# Power_and_Connectors.net
KiCad netlist of a schematic drawn in Altium Designer
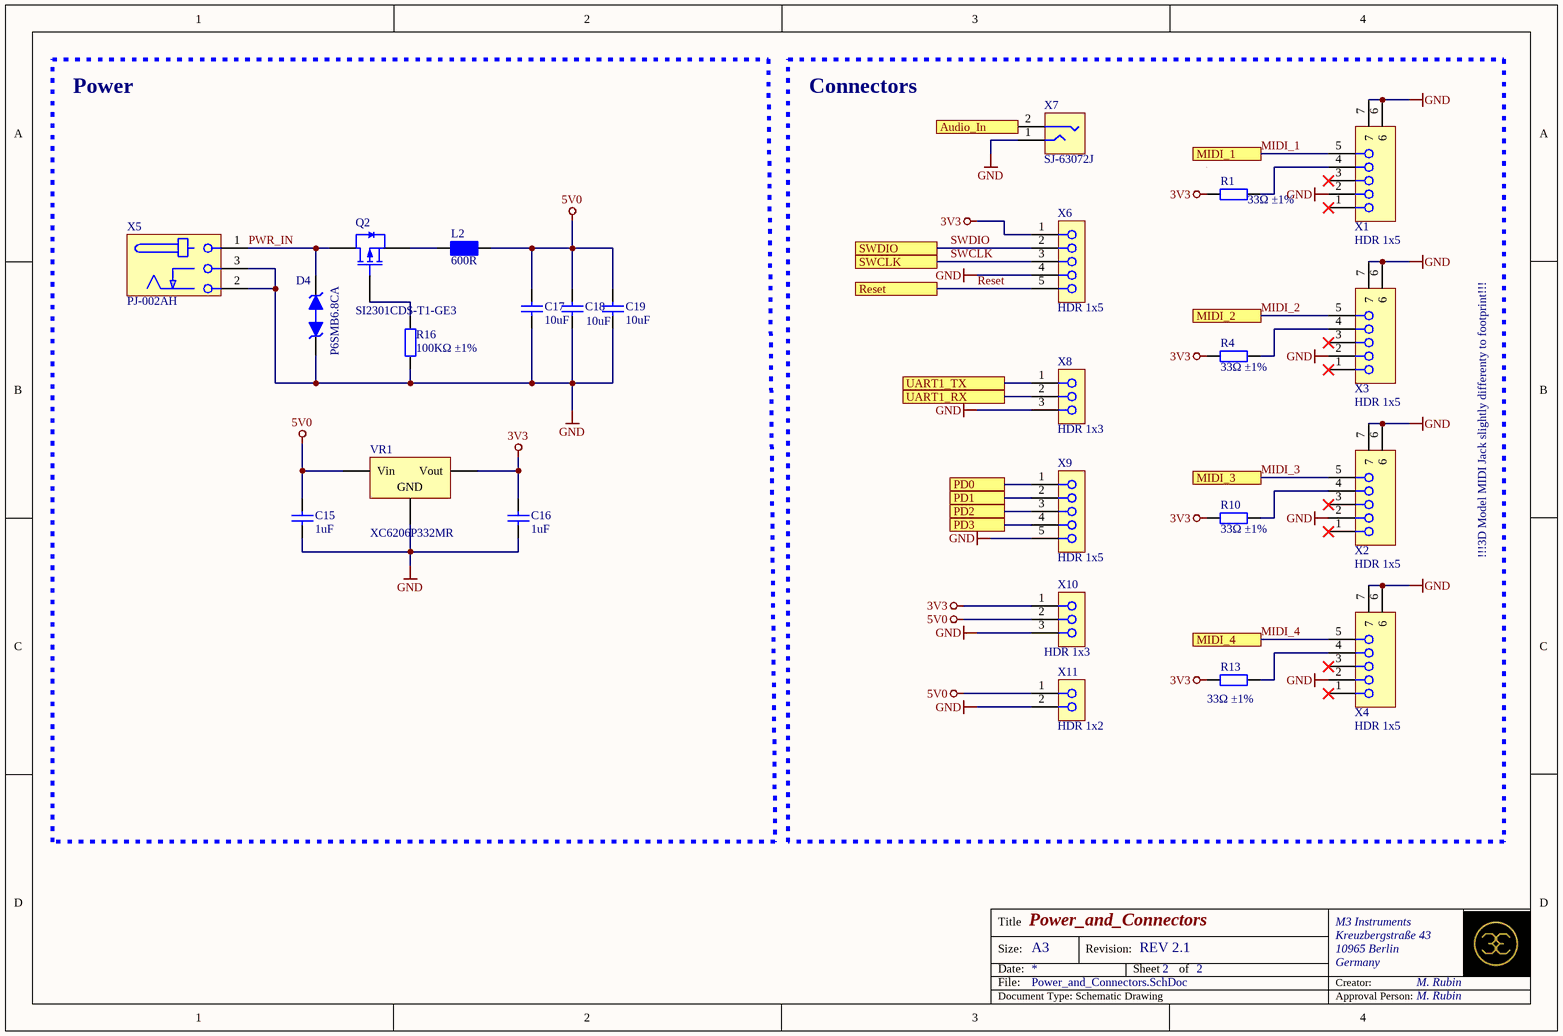
[diagram p0: Power_and_Connectors.SchDoc]

(export (version "E")
  (design (tool "Eeschema 10.0.6"))
  (components
    (comp (ref "C15")
      (value "1uF")
      (footprint "0603_C")
      (description "Chip capacitors")
      (fields
        (field (name "MANUFACTURER") "Samsung Electro-Mechanics")
        (field (name "PARTNUMBER") "CL10A105KB8NNNC")
      )
      (libsource (lib "Cap") (part "0603 1uF (105) 10% 50V"))
    )
    (comp (ref "C16")
      (value "1uF")
      (footprint "0603_C")
      (description "Chip capacitors")
      (fields
        (field (name "MANUFACTURER") "Samsung Electro-Mechanics")
        (field (name "PARTNUMBER") "CL10A105KB8NNNC")
      )
      (libsource (lib "Cap") (part "0603 1uF (105) 10% 50V"))
    )
    (comp (ref "C17")
      (value "10uF")
      (footprint "0805_C")
      (description "Chip capacitors")
      (fields
        (field (name "MANUFACTURER") "Samsung Electro-Mechanics")
        (field (name "PARTNUMBER") "CL21A106KAYNNNE")
      )
      (libsource (lib "Cap") (part "0805 10uF (106) 10% 25V"))
    )
    (comp (ref "C18")
      (value "10uF")
      (footprint "0805_C")
      (description "Chip capacitors")
      (fields
        (field (name "MANUFACTURER") "Samsung Electro-Mechanics")
        (field (name "PARTNUMBER") "CL21A106KAYNNNE")
      )
      (libsource (lib "Cap") (part "0805 10uF (106) 10% 25V"))
    )
    (comp (ref "C19")
      (value "10uF")
      (footprint "0805_C")
      (description "Chip capacitors")
      (fields
        (field (name "MANUFACTURER") "Samsung Electro-Mechanics")
        (field (name "PARTNUMBER") "CL21A106KAYNNNE")
      )
      (libsource (lib "Cap") (part "0805 10uF (106) 10% 25V"))
    )
    (comp (ref "D4")
      (value "P6SMB6.8CA")
      (footprint "SMB(DO-214AA)_S1")
      (description "TVS 6.8V")
      (fields (field (name "MANUFACTURER") "Brightking Elec"))
      (libsource (lib "Diodes") (part "DIO_P6SMB6.8CA"))
    )
    (comp (ref "L2")
      (value "600R")
      (footprint "INDC2012X85N")
      (description "Ferrite Beads 0805 600 OHM")
      (fields
        (field (name "MANUFACTURER") "Murata Electronics")
        (field (name "MANUFACTURER PART NUMBER") "BLM21AG601SN1D")
      )
      (libsource (lib "Inductors") (part "FB_600R_600mA_0805"))
    )
    (comp (ref "Q2")
      (value "SI2301CDS-T1-GE3")
      (footprint "SOT-23(SOT-23-3)")
      (description "MOS(场效应管)")
      (libsource (lib "MOS") (part "SI2301CDS-T1-GE3"))
    )
    (comp (ref "R1")
      (value "33Ω ±1%")
      (footprint "0603_R")
      (description "Chip resistor")
      (fields (field (name "MANUFACTURER") "Uniroyal Elec") (field (name "PARTNUMBER") "0603WAF330JT5E"))
      (libsource (lib "RES") (part "0603 33R (33R0) 1%"))
    )
    (comp (ref "R4")
      (value "33Ω ±1%")
      (footprint "0603_R")
      (description "Chip resistor")
      (fields (field (name "MANUFACTURER") "Uniroyal Elec") (field (name "PARTNUMBER") "0603WAF330JT5E"))
      (libsource (lib "RES") (part "0603 33R (33R0) 1%"))
    )
    (comp (ref "R10")
      (value "33Ω ±1%")
      (footprint "0603_R")
      (description "Chip resistor")
      (fields (field (name "MANUFACTURER") "Uniroyal Elec") (field (name "PARTNUMBER") "0603WAF330JT5E"))
      (libsource (lib "RES") (part "0603 33R (33R0) 1%"))
    )
    (comp (ref "R13")
      (value "33Ω ±1%")
      (footprint "0603_R")
      (description "Chip resistor")
      (fields (field (name "MANUFACTURER") "Uniroyal Elec") (field (name "PARTNUMBER") "0603WAF330JT5E"))
      (libsource (lib "RES") (part "0603 33R (33R0) 1%"))
    )
    (comp (ref "R16")
      (value "100KΩ ±1%")
      (footprint "0603_R")
      (description "Chip resistor")
      (fields (field (name "MANUFACTURER") "Uniroyal Elec") (field (name "PARTNUMBER") "0603WAF1003T5E"))
      (libsource (lib "RES") (part "0603 100K (1003) 1%"))
    )
    (comp (ref "VR1")
      (value "XC6206P332MR")
      (footprint "SOT-23-3L")
      (description "低压差线性稳压(LDO)")
      (libsource (lib "LDO") (part "SOT-23 XC6206P332MR"))
    )
    (comp (ref "X1")
      (value "HDR 1x5")
      (footprint "MABP 5S")
      (description "Board-to-Board-Steckverbinder, 2.54 mm, 5 Kontakt(e), Stiftleiste 1-Reihig")
      (fields (field (name "MANUFACTURER") "BKL") (field (name "MANUFACTURER PART NUMBER") "MABP 5S"))
      (libsource (lib "Connectors") (part "CON_HEADER_1X5"))
    )
    (comp (ref "X2")
      (value "HDR 1x5")
      (footprint "MABP 5S")
      (description "Board-to-Board-Steckverbinder, 2.54 mm, 5 Kontakt(e), Stiftleiste 1-Reihig")
      (fields (field (name "MANUFACTURER") "BKL") (field (name "MANUFACTURER PART NUMBER") "MABP 5S"))
      (libsource (lib "Connectors") (part "CON_HEADER_1X5"))
    )
    (comp (ref "X3")
      (value "HDR 1x5")
      (footprint "MABP 5S")
      (description "Board-to-Board-Steckverbinder, 2.54 mm, 5 Kontakt(e), Stiftleiste 1-Reihig")
      (fields (field (name "MANUFACTURER") "BKL") (field (name "MANUFACTURER PART NUMBER") "MABP 5S"))
      (libsource (lib "Connectors") (part "CON_HEADER_1X5"))
    )
    (comp (ref "X4")
      (value "HDR 1x5")
      (footprint "MABP 5S")
      (description "Board-to-Board-Steckverbinder, 2.54 mm, 5 Kontakt(e), Stiftleiste 1-Reihig")
      (fields (field (name "MANUFACTURER") "BKL") (field (name "MANUFACTURER PART NUMBER") "MABP 5S"))
      (libsource (lib "Connectors") (part "CON_HEADER_1X5"))
    )
    (comp (ref "X5")
      (value "PJ-002AH")
      (footprint "PJ3L1400H110")
      (description "DC Power Connectors Power Jacks, Inside Contact Diameter 2mm, Outside Contact Diameter 6,5mm")
      (fields
        (field (name "MANUFACTURER") "CUI Devices")
        (field (name "LUMIRA PART NUMBER") "S-QMS-SPEC-32532")
      )
      (libsource (lib "_CONNECTORS") (part "PJ-002AH"))
    )
    (comp (ref "X6")
      (value "HDR 1x5")
      (footprint "CON_HEADER2.54_1x5W")
      (description "Board-to-Board-Steckverbinder, 2.54 mm, 5 Kontakt(e), Stiftleiste 1-Reihig")
      (fields
        (field (name "MANUFACTURER") "Samtec")
        (field (name "MANUFACTURER PART NUMBER") "TSW-105-07-T-S")
      )
      (libsource (lib "_CONNECTORS") (part "CON_HEADER_1X5"))
    )
    (comp (ref "X7")
      (value "SJ-63072J")
      (footprint "CUI_SJ-63072J")
      (description "Telefon-Steckverbinder 1/4\"JACK HOR CHASIS CON PLSTC MNT")
      (fields (field (name "MANUFACTURER") "CUI Devices"))
      (libsource (lib "Connectors") (part "Phone_Jack_1/4"))
    )
    (comp (ref "X8")
      (value "HDR 1x3")
      (footprint "CON_HEADER2.54_1x3W")
      (description "Board-to-Board-Steckverbinder, 2.54 mm, 3 Kontakt(e), Stiftleiste 1-Reihig")
      (fields
        (field (name "MANUFACTURER") "Samtec")
        (field (name "MANUFACTURER PART NUMBER") "TSW-103-07-T-S")
      )
      (libsource (lib "_CONNECTORS") (part "CON_HEADER_1X3"))
    )
    (comp (ref "X9")
      (value "HDR 1x5")
      (footprint "CON_HEADER2.54_1x5W")
      (description "Board-to-Board-Steckverbinder, 2.54 mm, 5 Kontakt(e), Stiftleiste 1-Reihig")
      (fields
        (field (name "MANUFACTURER") "Samtec")
        (field (name "MANUFACTURER PART NUMBER") "TSW-105-07-T-S")
      )
      (libsource (lib "_CONNECTORS") (part "CON_HEADER_1X5"))
    )
    (comp (ref "X10")
      (value "HDR 1x3")
      (footprint "CON_HEADER2.54_1x3W")
      (description "Board-to-Board-Steckverbinder, 2.54 mm, 3 Kontakt(e), Stiftleiste 1-Reihig")
      (fields
        (field (name "MANUFACTURER") "Samtec")
        (field (name "MANUFACTURER PART NUMBER") "TSW-103-07-T-S")
      )
      (libsource (lib "_CONNECTORS") (part "CON_HEADER_1X3"))
    )
    (comp (ref "X11")
      (value "HDR 1x2")
      (footprint "CON_HEADER2.54_1x2W")
      (description "Board-to-Board-Steckverbinder, 2.54 mm, 2 Kontakt(e), Stiftleiste 1-Reihig")
      (fields
        (field (name "MANUFACTURER") "Samtec")
        (field (name "MANUFACTURER PART NUMBER") "TSW-102-07-T-S")
      )
      (libsource (lib "Connectors") (part "CON_HEADER_1X2"))
    )
  )
  (nets
    (net (code "1") (name "/Audio_In") (class "Default")
      (node (ref "X7") (pin "2") (pinfunction "2_2") (pintype "passive"))
    )
    (net (code "2") (name "/MIDI_1") (class "Default")
      (node (ref "X1") (pin "5") (pinfunction "5_5") (pintype "passive"))
    )
    (net (code "3") (name "/MIDI_2") (class "Default")
      (node (ref "X3") (pin "5") (pinfunction "5_5") (pintype "passive"))
    )
    (net (code "4") (name "/MIDI_3") (class "Default")
      (node (ref "X2") (pin "5") (pinfunction "5_5") (pintype "passive"))
    )
    (net (code "5") (name "/MIDI_4") (class "Default")
      (node (ref "X4") (pin "5") (pinfunction "5_5") (pintype "passive"))
    )
    (net (code "6") (name "/PD0") (class "Default")
      (node (ref "X9") (pin "1") (pinfunction "1_1") (pintype "passive"))
    )
    (net (code "7") (name "/PD1") (class "Default")
      (node (ref "X9") (pin "2") (pinfunction "2_2") (pintype "passive"))
    )
    (net (code "8") (name "/PD2") (class "Default")
      (node (ref "X9") (pin "3") (pinfunction "3_3") (pintype "passive"))
    )
    (net (code "9") (name "/PD3") (class "Default")
      (node (ref "X9") (pin "4") (pinfunction "4_4") (pintype "passive"))
    )
    (net (code "10") (name "/PWR_IN") (class "Default")
      (node (ref "D4") (pin "A2") (pinfunction "A2_A2") (pintype "passive"))
      (node (ref "Q2") (pin "3") (pinfunction "D_3") (pintype "passive"))
      (node (ref "X5") (pin "1") (pinfunction "1_1") (pintype "passive"))
    )
    (net (code "11") (name "/Reset") (class "Default")
      (node (ref "X6") (pin "5") (pinfunction "5_5") (pintype "passive"))
    )
    (net (code "12") (name "/SWCLK") (class "Default")
      (node (ref "X6") (pin "3") (pinfunction "3_3") (pintype "passive"))
    )
    (net (code "13") (name "/SWDIO") (class "Default")
      (node (ref "X6") (pin "2") (pinfunction "2_2") (pintype "passive"))
    )
    (net (code "14") (name "/UART1_RX") (class "Default")
      (node (ref "X8") (pin "2") (pinfunction "2_2") (pintype "passive"))
    )
    (net (code "15") (name "/UART1_TX") (class "Default")
      (node (ref "X8") (pin "1") (pinfunction "1_1") (pintype "passive"))
    )
    (net (code "16") (name "3V3") (class "Default")
      (node (ref "C16") (pin "2") (pinfunction "2_2") (pintype "passive"))
      (node (ref "R1") (pin "1") (pinfunction "1_1") (pintype "passive"))
      (node (ref "R10") (pin "1") (pinfunction "1_1") (pintype "passive"))
      (node (ref "R13") (pin "1") (pinfunction "1_1") (pintype "passive"))
      (node (ref "R4") (pin "1") (pinfunction "1_1") (pintype "passive"))
      (node (ref "VR1") (pin "2") (pinfunction "Vout_2") (pintype "passive"))
      (node (ref "X10") (pin "1") (pinfunction "1_1") (pintype "passive"))
      (node (ref "X6") (pin "1") (pinfunction "1_1") (pintype "passive"))
    )
    (net (code "17") (name "5V0") (class "Default")
      (node (ref "C15") (pin "2") (pinfunction "2_2") (pintype "passive"))
      (node (ref "C17") (pin "2") (pinfunction "2_2") (pintype "passive"))
      (node (ref "C18") (pin "2") (pinfunction "2_2") (pintype "passive"))
      (node (ref "C19") (pin "2") (pinfunction "2_2") (pintype "passive"))
      (node (ref "L2") (pin "2") (pinfunction "2_2") (pintype "passive"))
      (node (ref "VR1") (pin "3") (pinfunction "Vin_3") (pintype "passive"))
      (node (ref "X10") (pin "2") (pinfunction "2_2") (pintype "passive"))
      (node (ref "X11") (pin "1") (pinfunction "1_1") (pintype "passive"))
    )
    (net (code "18") (name "GND") (class "Default")
      (node (ref "C15") (pin "1") (pinfunction "1_1") (pintype "passive"))
      (node (ref "C16") (pin "1") (pinfunction "1_1") (pintype "passive"))
      (node (ref "C17") (pin "1") (pinfunction "1_1") (pintype "passive"))
      (node (ref "C18") (pin "1") (pinfunction "1_1") (pintype "passive"))
      (node (ref "C19") (pin "1") (pinfunction "1_1") (pintype "passive"))
      (node (ref "D4") (pin "A1") (pinfunction "A1_A1") (pintype "passive"))
      (node (ref "R16") (pin "1") (pinfunction "1_1") (pintype "passive"))
      (node (ref "VR1") (pin "1") (pinfunction "GND_1") (pintype "passive"))
      (node (ref "X1") (pin "2") (pinfunction "2_2") (pintype "passive"))
      (node (ref "X1") (pin "6") (pinfunction "6_6") (pintype "passive"))
      (node (ref "X1") (pin "7") (pinfunction "7_7") (pintype "passive"))
      (node (ref "X10") (pin "3") (pinfunction "3_3") (pintype "passive"))
      (node (ref "X11") (pin "2") (pinfunction "2_2") (pintype "passive"))
      (node (ref "X2") (pin "2") (pinfunction "2_2") (pintype "passive"))
      (node (ref "X2") (pin "6") (pinfunction "6_6") (pintype "passive"))
      (node (ref "X2") (pin "7") (pinfunction "7_7") (pintype "passive"))
      (node (ref "X3") (pin "2") (pinfunction "2_2") (pintype "passive"))
      (node (ref "X3") (pin "6") (pinfunction "6_6") (pintype "passive"))
      (node (ref "X3") (pin "7") (pinfunction "7_7") (pintype "passive"))
      (node (ref "X4") (pin "2") (pinfunction "2_2") (pintype "passive"))
      (node (ref "X4") (pin "6") (pinfunction "6_6") (pintype "passive"))
      (node (ref "X4") (pin "7") (pinfunction "7_7") (pintype "passive"))
      (node (ref "X5") (pin "2") (pinfunction "2_2") (pintype "passive"))
      (node (ref "X5") (pin "3") (pinfunction "3_3") (pintype "passive"))
      (node (ref "X6") (pin "4") (pinfunction "4_4") (pintype "passive"))
      (node (ref "X7") (pin "1") (pinfunction "1_1") (pintype "passive"))
      (node (ref "X8") (pin "3") (pinfunction "3_3") (pintype "passive"))
      (node (ref "X9") (pin "5") (pinfunction "5_5") (pintype "passive"))
    )
    (net (code "19") (name "Net-(Q2-G)") (class "Default")
      (node (ref "Q2") (pin "1") (pinfunction "G_1") (pintype "passive"))
      (node (ref "R16") (pin "2") (pinfunction "2_2") (pintype "passive"))
    )
    (net (code "20") (name "Net-(Q2-S)") (class "Default")
      (node (ref "L2") (pin "1") (pinfunction "1_1") (pintype "passive"))
      (node (ref "Q2") (pin "2") (pinfunction "S_2") (pintype "passive"))
    )
    (net (code "21") (name "Net-(R1-Pad2)") (class "Default")
      (node (ref "R1") (pin "2") (pinfunction "2_2") (pintype "passive"))
      (node (ref "X1") (pin "4") (pinfunction "4_4") (pintype "passive"))
    )
    (net (code "22") (name "Net-(R4-Pad2)") (class "Default")
      (node (ref "R4") (pin "2") (pinfunction "2_2") (pintype "passive"))
      (node (ref "X3") (pin "4") (pinfunction "4_4") (pintype "passive"))
    )
    (net (code "23") (name "Net-(R10-Pad2)") (class "Default")
      (node (ref "R10") (pin "2") (pinfunction "2_2") (pintype "passive"))
      (node (ref "X2") (pin "4") (pinfunction "4_4") (pintype "passive"))
    )
    (net (code "24") (name "Net-(R13-Pad2)") (class "Default")
      (node (ref "R13") (pin "2") (pinfunction "2_2") (pintype "passive"))
      (node (ref "X4") (pin "4") (pinfunction "4_4") (pintype "passive"))
    )
    (net (code "25") (name "unconnected-(X1-Pad1)") (class "Default")
      (node (ref "X1") (pin "1") (pinfunction "1_1") (pintype "passive+no_connect"))
    )
    (net (code "26") (name "unconnected-(X1-Pad3)") (class "Default")
      (node (ref "X1") (pin "3") (pinfunction "3_3") (pintype "passive+no_connect"))
    )
    (net (code "27") (name "unconnected-(X2-Pad1)") (class "Default")
      (node (ref "X2") (pin "1") (pinfunction "1_1") (pintype "passive+no_connect"))
    )
    (net (code "28") (name "unconnected-(X2-Pad3)") (class "Default")
      (node (ref "X2") (pin "3") (pinfunction "3_3") (pintype "passive+no_connect"))
    )
    (net (code "29") (name "unconnected-(X3-Pad1)") (class "Default")
      (node (ref "X3") (pin "1") (pinfunction "1_1") (pintype "passive+no_connect"))
    )
    (net (code "30") (name "unconnected-(X3-Pad3)") (class "Default")
      (node (ref "X3") (pin "3") (pinfunction "3_3") (pintype "passive+no_connect"))
    )
    (net (code "31") (name "unconnected-(X4-Pad1)") (class "Default")
      (node (ref "X4") (pin "1") (pinfunction "1_1") (pintype "passive+no_connect"))
    )
    (net (code "32") (name "unconnected-(X4-Pad3)") (class "Default")
      (node (ref "X4") (pin "3") (pinfunction "3_3") (pintype "passive+no_connect"))
    )
  )
)
